# COMMS.net
KiCad netlist of a schematic drawn in Altium Designer
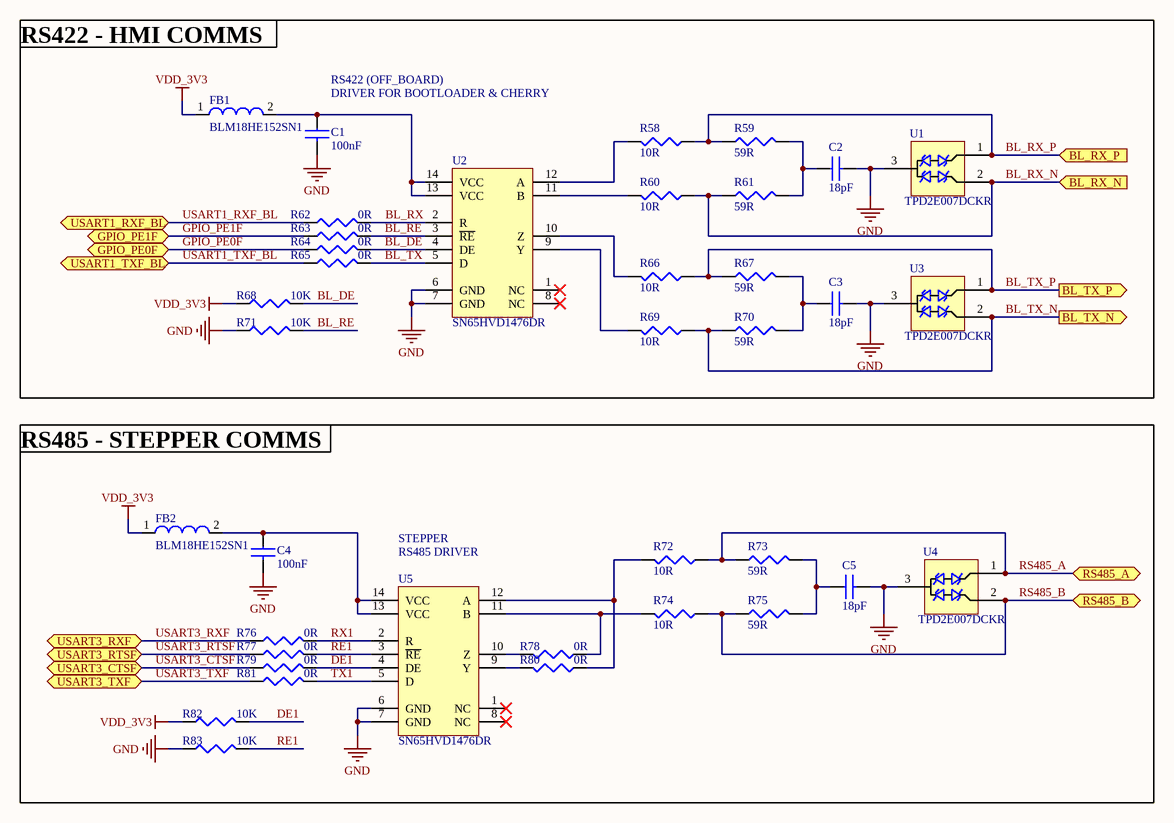
[diagram p0: COMMS.SchDoc]

(export (version "E")
  (design (tool "Eeschema 10.0.6"))
  (components
    (comp (ref "C1")
      (value "100nF")
      (footprint "CC0402")
      (description "CAP CER 0.1UF 50V 10% X7R 0402")
      (fields (field (name "MANUFACTURER") "Murata") (field (name "PARTNUMBER") "GCM155R71H104KE02D"))
      (libsource (lib "ERD TiAm") (part "CAP CER 0.1UF 10V 10% X5R 0402"))
    )
    (comp (ref "C2")
      (value "18pF")
      (footprint "CC0402")
      (description "CAP CER 18pF 50V 5% C0G 0402")
      (fields (field (name "MANUFACTURER") "AVX") (field (name "PARTNUMBER") "GJM1555C1H180FB01D"))
      (libsource (lib "ERD TiAm") (part "CAP CER 2.2UF 6.3V 10% X5R 0402"))
    )
    (comp (ref "C3")
      (value "18pF")
      (footprint "CC0402")
      (description "CAP CER 18pF 50V 5% C0G 0402")
      (fields (field (name "MANUFACTURER") "AVX") (field (name "PARTNUMBER") "GJM1555C1H180FB01D"))
      (libsource (lib "ERD TiAm") (part "CAP CER 2.2UF 6.3V 10% X5R 0402"))
    )
    (comp (ref "C4")
      (value "100nF")
      (footprint "CC0402")
      (description "CAP CER 0.1UF 50V 10% X7R 0402")
      (fields (field (name "MANUFACTURER") "Murata") (field (name "PARTNUMBER") "GCM155R71H104KE02D"))
      (libsource (lib "ERD TiAm") (part "CAP CER 0.1UF 10V 10% X5R 0402"))
    )
    (comp (ref "C5")
      (value "18pF")
      (footprint "CC0402")
      (description "CAP CER 18pF 50V 5% C0G 0402")
      (fields (field (name "MANUFACTURER") "AVX") (field (name "PARTNUMBER") "GJM1555C1H180FB01D"))
      (libsource (lib "ERD TiAm") (part "CAP CER 2.2UF 6.3V 10% X5R 0402"))
    )
    (comp (ref "FB1")
      (value "BLM18HE152SN1")
      (footprint "LC0603")
      (description "FERRITE, 500mA, 500mOHM, 0603")
      (libsource (lib "BEAGLEBONEBLACK_REV A5B") (part "FER_180_200_0"))
    )
    (comp (ref "FB2")
      (value "BLM18HE152SN1")
      (footprint "LC0603")
      (description "FERRITE, 500mA, 500mOHM, 0603")
      (libsource (lib "BEAGLEBONEBLACK_REV A5B") (part "FER_180_200_0"))
    )
    (comp (ref "R58")
      (value "10R")
      (footprint "RC0603")
      (description "RES 10 OHM 1/10W 5% 0603 SMD")
      (fields (field (name "MANUFACTURER") "Yageo") (field (name "PARTNUMBER") "RC0603JR-0710RL"))
      (libsource (lib "ERD TiAm") (part "RES_10K_1/16W_1%_0402"))
    )
    (comp (ref "R59")
      (value "59R")
      (footprint "RC0402")
      (description "RES, 59 OHM, 1/16W, 1%, 0402")
      (fields (field (name "MANUFACTURER") "Yageo") (field (name "PARTNUMBER") "RC0402FR-0759RL"))
      (libsource (lib "ERD TiAm") (part "RES_10K_1/16W_1%_0402"))
    )
    (comp (ref "R60")
      (value "10R")
      (footprint "RC0603")
      (description "RES 10 OHM 1/10W 5% 0603 SMD")
      (fields (field (name "MANUFACTURER") "Yageo") (field (name "PARTNUMBER") "RC0603JR-0710RL"))
      (libsource (lib "ERD TiAm") (part "RES_10K_1/16W_1%_0402"))
    )
    (comp (ref "R61")
      (value "59R")
      (footprint "RC0402")
      (description "RES, 59 OHM, 1/16W, 1%, 0402")
      (fields (field (name "MANUFACTURER") "Yageo") (field (name "PARTNUMBER") "RC0402FR-0759RL"))
      (libsource (lib "ERD TiAm") (part "RES_10K_1/16W_1%_0402"))
    )
    (comp (ref "R62")
      (value "0R")
      (footprint "RC0402")
      (description "RES, 0 OHM, 1/16W, 1%, 0402")
      (fields (field (name "MANUFACTURER") "Yageo") (field (name "PARTNUMBER") "RC0402FR-070RL"))
      (libsource (lib "ERD TiAm") (part "RES_10K_1/16W_1%_0402"))
    )
    (comp (ref "R63")
      (value "0R")
      (footprint "RC0402")
      (description "RES, 0 OHM, 1/16W, 1%, 0402")
      (fields (field (name "MANUFACTURER") "Yageo") (field (name "PARTNUMBER") "RC0402FR-070RL"))
      (libsource (lib "ERD TiAm") (part "RES_10K_1/16W_1%_0402"))
    )
    (comp (ref "R64")
      (value "0R")
      (footprint "RC0402")
      (description "RES, 0 OHM, 1/16W, 1%, 0402")
      (fields (field (name "MANUFACTURER") "Yageo") (field (name "PARTNUMBER") "RC0402FR-070RL"))
      (libsource (lib "ERD TiAm") (part "RES_10K_1/16W_1%_0402"))
    )
    (comp (ref "R65")
      (value "0R")
      (footprint "RC0402")
      (description "RES, 0 OHM, 1/16W, 1%, 0402")
      (fields (field (name "MANUFACTURER") "Yageo") (field (name "PARTNUMBER") "RC0402FR-070RL"))
      (libsource (lib "ERD TiAm") (part "RES_10K_1/16W_1%_0402"))
    )
    (comp (ref "R66")
      (value "10R")
      (footprint "RC0603")
      (description "RES 10 OHM 1/10W 5% 0603 SMD")
      (fields (field (name "MANUFACTURER") "Yageo") (field (name "PARTNUMBER") "RC0603JR-0710RL"))
      (libsource (lib "ERD TiAm") (part "RES_10K_1/16W_1%_0402"))
    )
    (comp (ref "R67")
      (value "59R")
      (footprint "RC0402")
      (description "RES, 59 OHM, 1/16W, 1%, 0402")
      (fields (field (name "MANUFACTURER") "Yageo") (field (name "PARTNUMBER") "RC0402FR-0759RL"))
      (libsource (lib "ERD TiAm") (part "RES_10K_1/16W_1%_0402"))
    )
    (comp (ref "R68")
      (value "10K")
      (footprint "RC0402")
      (description "RES, 10K OHM, 1/16W, 1%, 0402")
      (fields (field (name "MANUFACTURER") "Yageo") (field (name "PART NUMBER") "RC0402FR-0710KL"))
      (libsource (lib "ERD TiAm") (part "RES_10K_1/16W_1%_0402"))
    )
    (comp (ref "R69")
      (value "10R")
      (footprint "RC0603")
      (description "RES 10 OHM 1/10W 5% 0603 SMD")
      (fields (field (name "MANUFACTURER") "Yageo") (field (name "PARTNUMBER") "RC0603JR-0710RL"))
      (libsource (lib "ERD TiAm") (part "RES_10K_1/16W_1%_0402"))
    )
    (comp (ref "R70")
      (value "59R")
      (footprint "RC0402")
      (description "RES, 59 OHM, 1/16W, 1%, 0402")
      (fields (field (name "MANUFACTURER") "Yageo") (field (name "PARTNUMBER") "RC0402FR-0759RL"))
      (libsource (lib "ERD TiAm") (part "RES_10K_1/16W_1%_0402"))
    )
    (comp (ref "R71")
      (value "10K")
      (footprint "RC0402")
      (description "RES, 10K OHM, 1/16W, 1%, 0402")
      (fields (field (name "MANUFACTURER") "Yageo") (field (name "PART NUMBER") "RC0402FR-0710KL"))
      (libsource (lib "ERD TiAm") (part "RES_10K_1/16W_1%_0402"))
    )
    (comp (ref "R72")
      (value "10R")
      (footprint "RC0603")
      (description "RES 10 OHM 1/10W 5% 0603 SMD")
      (fields (field (name "MANUFACTURER") "Yageo") (field (name "PARTNUMBER") "RC0603JR-0710RL"))
      (libsource (lib "ERD TiAm") (part "RES_10K_1/16W_1%_0402"))
    )
    (comp (ref "R73")
      (value "59R")
      (footprint "RC0402")
      (description "RES, 59 OHM, 1/16W, 1%, 0402")
      (fields (field (name "MANUFACTURER") "Yageo") (field (name "PARTNUMBER") "RC0402FR-0759RL"))
      (libsource (lib "ERD TiAm") (part "RES_10K_1/16W_1%_0402"))
    )
    (comp (ref "R74")
      (value "10R")
      (footprint "RC0603")
      (description "RES 10 OHM 1/10W 5% 0603 SMD")
      (fields (field (name "MANUFACTURER") "Yageo") (field (name "PARTNUMBER") "RC0603JR-0710RL"))
      (libsource (lib "ERD TiAm") (part "RES_10K_1/16W_1%_0402"))
    )
    (comp (ref "R75")
      (value "59R")
      (footprint "RC0402")
      (description "RES, 59 OHM, 1/16W, 1%, 0402")
      (fields (field (name "MANUFACTURER") "Yageo") (field (name "PARTNUMBER") "RC0402FR-0759RL"))
      (libsource (lib "ERD TiAm") (part "RES_10K_1/16W_1%_0402"))
    )
    (comp (ref "R76")
      (value "0R")
      (footprint "RC0402")
      (description "RES, 0 OHM, 1/16W, 1%, 0402")
      (fields (field (name "MANUFACTURER") "Yageo") (field (name "PARTNUMBER") "RC0402FR-070RL"))
      (libsource (lib "ERD TiAm") (part "RES_10K_1/16W_1%_0402"))
    )
    (comp (ref "R77")
      (value "0R")
      (footprint "RC0402")
      (description "RES, 0 OHM, 1/16W, 1%, 0402")
      (fields (field (name "MANUFACTURER") "Yageo") (field (name "PARTNUMBER") "RC0402FR-070RL"))
      (libsource (lib "ERD TiAm") (part "RES_10K_1/16W_1%_0402"))
    )
    (comp (ref "R78")
      (value "0R")
      (footprint "RC0402")
      (description "RES, 0 OHM, 1/16W, 1%, 0402")
      (fields (field (name "MANUFACTURER") "Yageo") (field (name "PARTNUMBER") "RC0402FR-070RL"))
      (libsource (lib "ERD TiAm") (part "RES_10K_1/16W_1%_0402"))
    )
    (comp (ref "R79")
      (value "0R")
      (footprint "RC0402")
      (description "RES, 0 OHM, 1/16W, 1%, 0402")
      (fields (field (name "MANUFACTURER") "Yageo") (field (name "PARTNUMBER") "RC0402FR-070RL"))
      (libsource (lib "ERD TiAm") (part "RES_10K_1/16W_1%_0402"))
    )
    (comp (ref "R80")
      (value "0R")
      (footprint "RC0402")
      (description "RES, 0 OHM, 1/16W, 1%, 0402")
      (fields (field (name "MANUFACTURER") "Yageo") (field (name "PARTNUMBER") "RC0402FR-070RL"))
      (libsource (lib "ERD TiAm") (part "RES_10K_1/16W_1%_0402"))
    )
    (comp (ref "R81")
      (value "0R")
      (footprint "RC0402")
      (description "RES, 0 OHM, 1/16W, 1%, 0402")
      (fields (field (name "MANUFACTURER") "Yageo") (field (name "PARTNUMBER") "RC0402FR-070RL"))
      (libsource (lib "ERD TiAm") (part "RES_10K_1/16W_1%_0402"))
    )
    (comp (ref "R82")
      (value "10K")
      (footprint "RC0402")
      (description "RES, 10K OHM, 1/16W, 1%, 0402")
      (fields (field (name "MANUFACTURER") "Yageo") (field (name "PART NUMBER") "RC0402FR-0710KL"))
      (libsource (lib "ERD TiAm") (part "RES_10K_1/16W_1%_0402"))
    )
    (comp (ref "R83")
      (value "10K")
      (footprint "RC0402")
      (description "RES, 10K OHM, 1/16W, 1%, 0402")
      (fields (field (name "MANUFACTURER") "Yageo") (field (name "PART NUMBER") "RC0402FR-0710KL"))
      (libsource (lib "ERD TiAm") (part "RES_10K_1/16W_1%_0402"))
    )
    (comp (ref "U1")
      (value "TPD2E007DCKR")
      (footprint "SOT23 - DGK")
      (description "DIODE, TVS, 2-CHANNEL ESD PROTECTION ARRAY, SOT23")
      (fields (field (name "MANUFACTURER") "Texas Instruments"))
      (libsource (lib "ERD TiAm") (part "TPD2E007"))
    )
    (comp (ref "U2")
      (value "SN65HVD1476DR")
      (footprint "SOIC-14")
      (description "Transceiver, RS-485/422, Full-Duplex, SOIC-14")
      (libsource (lib "ERD TiAm") (part "SN65HVD1476"))
    )
    (comp (ref "U3")
      (value "TPD2E007DCKR")
      (footprint "SOT23 - DGK")
      (description "DIODE, TVS, 2-CHANNEL ESD PROTECTION ARRAY, SOT23")
      (fields (field (name "MANUFACTURER") "Texas Instruments"))
      (libsource (lib "ERD TiAm") (part "TPD2E007"))
    )
    (comp (ref "U4")
      (value "TPD2E007DCKR")
      (footprint "SOT23 - DGK")
      (description "DIODE, TVS, 2-CHANNEL ESD PROTECTION ARRAY, SOT23")
      (fields (field (name "MANUFACTURER") "Texas Instruments"))
      (libsource (lib "ERD TiAm") (part "TPD2E007"))
    )
    (comp (ref "U5")
      (value "SN65HVD1476DR")
      (footprint "SOIC-14")
      (description "Transceiver, RS-485/422, Full-Duplex, SOIC-14")
      (libsource (lib "ERD TiAm") (part "SN65HVD1476"))
    )
  )
  (nets
    (net (code "1") (name "/BL_DE") (class "Default")
      (node (ref "R64") (pin "2") (pinfunction "2_2") (pintype "passive"))
      (node (ref "R68") (pin "2") (pinfunction "2_2") (pintype "passive"))
      (node (ref "U2") (pin "4") (pinfunction "DE_4") (pintype "passive"))
    )
    (net (code "2") (name "/BL_RE") (class "Default")
      (node (ref "R63") (pin "2") (pinfunction "2_2") (pintype "passive"))
      (node (ref "R71") (pin "2") (pinfunction "2_2") (pintype "passive"))
      (node (ref "U2") (pin "3") (pinfunction "~{RE}_3") (pintype "passive"))
    )
    (net (code "3") (name "/BL_RX") (class "Default")
      (node (ref "R62") (pin "2") (pinfunction "2_2") (pintype "passive"))
      (node (ref "U2") (pin "2") (pinfunction "R_2") (pintype "passive"))
    )
    (net (code "4") (name "/BL_RX_N") (class "Default")
      (node (ref "R60") (pin "1") (pinfunction "1_1") (pintype "passive"))
      (node (ref "R61") (pin "1") (pinfunction "1_1") (pintype "passive"))
      (node (ref "U1") (pin "2") (pinfunction "IO2_2") (pintype "passive"))
    )
    (net (code "5") (name "/BL_RX_P") (class "Default")
      (node (ref "R58") (pin "1") (pinfunction "1_1") (pintype "passive"))
      (node (ref "R59") (pin "1") (pinfunction "1_1") (pintype "passive"))
      (node (ref "U1") (pin "1") (pinfunction "IO1_1") (pintype "passive"))
    )
    (net (code "6") (name "/BL_TX") (class "Default")
      (node (ref "R65") (pin "2") (pinfunction "2_2") (pintype "passive"))
      (node (ref "U2") (pin "5") (pinfunction "D_5") (pintype "passive"))
    )
    (net (code "7") (name "/BL_TX_N") (class "Default")
      (node (ref "R69") (pin "1") (pinfunction "1_1") (pintype "passive"))
      (node (ref "R70") (pin "1") (pinfunction "1_1") (pintype "passive"))
      (node (ref "U3") (pin "2") (pinfunction "IO2_2") (pintype "passive"))
    )
    (net (code "8") (name "/BL_TX_P") (class "Default")
      (node (ref "R66") (pin "1") (pinfunction "1_1") (pintype "passive"))
      (node (ref "R67") (pin "1") (pinfunction "1_1") (pintype "passive"))
      (node (ref "U3") (pin "1") (pinfunction "IO1_1") (pintype "passive"))
    )
    (net (code "9") (name "/DE1") (class "Default")
      (node (ref "R79") (pin "2") (pinfunction "2_2") (pintype "passive"))
      (node (ref "R82") (pin "2") (pinfunction "2_2") (pintype "passive"))
      (node (ref "U5") (pin "4") (pinfunction "DE_4") (pintype "passive"))
    )
    (net (code "10") (name "/GPIO_PE0F") (class "Default")
      (node (ref "R64") (pin "1") (pinfunction "1_1") (pintype "passive"))
    )
    (net (code "11") (name "/GPIO_PE1F") (class "Default")
      (node (ref "R63") (pin "1") (pinfunction "1_1") (pintype "passive"))
    )
    (net (code "12") (name "/RE1") (class "Default")
      (node (ref "R77") (pin "2") (pinfunction "2_2") (pintype "passive"))
      (node (ref "R83") (pin "2") (pinfunction "2_2") (pintype "passive"))
      (node (ref "U5") (pin "3") (pinfunction "~{RE}_3") (pintype "passive"))
    )
    (net (code "13") (name "/RS485_A") (class "Default")
      (node (ref "R72") (pin "1") (pinfunction "1_1") (pintype "passive"))
      (node (ref "R73") (pin "1") (pinfunction "1_1") (pintype "passive"))
      (node (ref "U4") (pin "1") (pinfunction "IO1_1") (pintype "passive"))
    )
    (net (code "14") (name "/RS485_B") (class "Default")
      (node (ref "R74") (pin "1") (pinfunction "1_1") (pintype "passive"))
      (node (ref "R75") (pin "1") (pinfunction "1_1") (pintype "passive"))
      (node (ref "U4") (pin "2") (pinfunction "IO2_2") (pintype "passive"))
    )
    (net (code "15") (name "/RX1") (class "Default")
      (node (ref "R76") (pin "2") (pinfunction "2_2") (pintype "passive"))
      (node (ref "U5") (pin "2") (pinfunction "R_2") (pintype "passive"))
    )
    (net (code "16") (name "/TX1") (class "Default")
      (node (ref "R81") (pin "2") (pinfunction "2_2") (pintype "passive"))
      (node (ref "U5") (pin "5") (pinfunction "D_5") (pintype "passive"))
    )
    (net (code "17") (name "/USART1_RXF_BL") (class "Default")
      (node (ref "R62") (pin "1") (pinfunction "1_1") (pintype "passive"))
    )
    (net (code "18") (name "/USART1_TXF_BL") (class "Default")
      (node (ref "R65") (pin "1") (pinfunction "1_1") (pintype "passive"))
    )
    (net (code "19") (name "/USART3_CTSF") (class "Default")
      (node (ref "R79") (pin "1") (pinfunction "1_1") (pintype "passive"))
    )
    (net (code "20") (name "/USART3_RTSF") (class "Default")
      (node (ref "R77") (pin "1") (pinfunction "1_1") (pintype "passive"))
    )
    (net (code "21") (name "/USART3_RXF") (class "Default")
      (node (ref "R76") (pin "1") (pinfunction "1_1") (pintype "passive"))
    )
    (net (code "22") (name "/USART3_TXF") (class "Default")
      (node (ref "R81") (pin "1") (pinfunction "1_1") (pintype "passive"))
    )
    (net (code "23") (name "GND") (class "Default")
      (node (ref "C1") (pin "2") (pinfunction "2_2") (pintype "passive"))
      (node (ref "C2") (pin "2") (pinfunction "2_2") (pintype "passive"))
      (node (ref "C3") (pin "2") (pinfunction "2_2") (pintype "passive"))
      (node (ref "C4") (pin "2") (pinfunction "2_2") (pintype "passive"))
      (node (ref "C5") (pin "2") (pinfunction "2_2") (pintype "passive"))
      (node (ref "R71") (pin "1") (pinfunction "1_1") (pintype "passive"))
      (node (ref "R83") (pin "1") (pinfunction "1_1") (pintype "passive"))
      (node (ref "U1") (pin "3") (pinfunction "GND_3") (pintype "passive"))
      (node (ref "U2") (pin "6") (pinfunction "GND_6") (pintype "passive"))
      (node (ref "U2") (pin "7") (pinfunction "GND_7") (pintype "passive"))
      (node (ref "U3") (pin "3") (pinfunction "GND_3") (pintype "passive"))
      (node (ref "U4") (pin "3") (pinfunction "GND_3") (pintype "passive"))
      (node (ref "U5") (pin "6") (pinfunction "GND_6") (pintype "passive"))
      (node (ref "U5") (pin "7") (pinfunction "GND_7") (pintype "passive"))
    )
    (net (code "24") (name "Net-(C1-Pad1)") (class "Default")
      (node (ref "C1") (pin "1") (pinfunction "1_1") (pintype "passive"))
      (node (ref "FB1") (pin "2") (pinfunction "2_2") (pintype "passive"))
      (node (ref "U2") (pin "13") (pinfunction "VCC_13") (pintype "passive"))
      (node (ref "U2") (pin "14") (pinfunction "VCC_14") (pintype "passive"))
    )
    (net (code "25") (name "Net-(C2-Pad1)") (class "Default")
      (node (ref "C2") (pin "1") (pinfunction "1_1") (pintype "passive"))
      (node (ref "R59") (pin "2") (pinfunction "2_2") (pintype "passive"))
      (node (ref "R61") (pin "2") (pinfunction "2_2") (pintype "passive"))
    )
    (net (code "26") (name "Net-(C3-Pad1)") (class "Default")
      (node (ref "C3") (pin "1") (pinfunction "1_1") (pintype "passive"))
      (node (ref "R67") (pin "2") (pinfunction "2_2") (pintype "passive"))
      (node (ref "R70") (pin "2") (pinfunction "2_2") (pintype "passive"))
    )
    (net (code "27") (name "Net-(C4-Pad1)") (class "Default")
      (node (ref "C4") (pin "1") (pinfunction "1_1") (pintype "passive"))
      (node (ref "FB2") (pin "2") (pinfunction "2_2") (pintype "passive"))
      (node (ref "U5") (pin "13") (pinfunction "VCC_13") (pintype "passive"))
      (node (ref "U5") (pin "14") (pinfunction "VCC_14") (pintype "passive"))
    )
    (net (code "28") (name "Net-(C5-Pad1)") (class "Default")
      (node (ref "C5") (pin "1") (pinfunction "1_1") (pintype "passive"))
      (node (ref "R73") (pin "2") (pinfunction "2_2") (pintype "passive"))
      (node (ref "R75") (pin "2") (pinfunction "2_2") (pintype "passive"))
    )
    (net (code "29") (name "Net-(U2-A)") (class "Default")
      (node (ref "R58") (pin "2") (pinfunction "2_2") (pintype "passive"))
      (node (ref "U2") (pin "12") (pinfunction "A_12") (pintype "passive"))
    )
    (net (code "30") (name "Net-(U2-B)") (class "Default")
      (node (ref "R60") (pin "2") (pinfunction "2_2") (pintype "passive"))
      (node (ref "U2") (pin "11") (pinfunction "B_11") (pintype "passive"))
    )
    (net (code "31") (name "Net-(U2-Y)") (class "Default")
      (node (ref "R69") (pin "2") (pinfunction "2_2") (pintype "passive"))
      (node (ref "U2") (pin "9") (pinfunction "Y_9") (pintype "passive"))
    )
    (net (code "32") (name "Net-(U2-Z)") (class "Default")
      (node (ref "R66") (pin "2") (pinfunction "2_2") (pintype "passive"))
      (node (ref "U2") (pin "10") (pinfunction "Z_10") (pintype "passive"))
    )
    (net (code "33") (name "Net-(U5-A)") (class "Default")
      (node (ref "R72") (pin "2") (pinfunction "2_2") (pintype "passive"))
      (node (ref "R80") (pin "1") (pinfunction "1_1") (pintype "passive"))
      (node (ref "U5") (pin "12") (pinfunction "A_12") (pintype "passive"))
    )
    (net (code "34") (name "Net-(U5-B)") (class "Default")
      (node (ref "R74") (pin "2") (pinfunction "2_2") (pintype "passive"))
      (node (ref "R78") (pin "1") (pinfunction "1_1") (pintype "passive"))
      (node (ref "U5") (pin "11") (pinfunction "B_11") (pintype "passive"))
    )
    (net (code "35") (name "Net-(U5-Y)") (class "Default")
      (node (ref "R80") (pin "2") (pinfunction "2_2") (pintype "passive"))
      (node (ref "U5") (pin "9") (pinfunction "Y_9") (pintype "passive"))
    )
    (net (code "36") (name "Net-(U5-Z)") (class "Default")
      (node (ref "R78") (pin "2") (pinfunction "2_2") (pintype "passive"))
      (node (ref "U5") (pin "10") (pinfunction "Z_10") (pintype "passive"))
    )
    (net (code "37") (name "VDD_3V3") (class "Default")
      (node (ref "FB1") (pin "1") (pinfunction "1_1") (pintype "passive"))
      (node (ref "FB2") (pin "1") (pinfunction "1_1") (pintype "passive"))
      (node (ref "R68") (pin "1") (pinfunction "1_1") (pintype "passive"))
      (node (ref "R82") (pin "1") (pinfunction "1_1") (pintype "passive"))
    )
    (net (code "38") (name "unconnected-(U2-NC-Pad1)") (class "Default")
      (node (ref "U2") (pin "1") (pinfunction "NC_1") (pintype "passive+no_connect"))
    )
    (net (code "39") (name "unconnected-(U2-NC-Pad8)") (class "Default")
      (node (ref "U2") (pin "8") (pinfunction "NC_8") (pintype "passive+no_connect"))
    )
    (net (code "40") (name "unconnected-(U5-NC-Pad1)") (class "Default")
      (node (ref "U5") (pin "1") (pinfunction "NC_1") (pintype "passive+no_connect"))
    )
    (net (code "41") (name "unconnected-(U5-NC-Pad8)") (class "Default")
      (node (ref "U5") (pin "8") (pinfunction "NC_8") (pintype "passive+no_connect"))
    )
  )
)
